# RGB_LED.net
KiCad netlist of a schematic drawn in Altium Designer
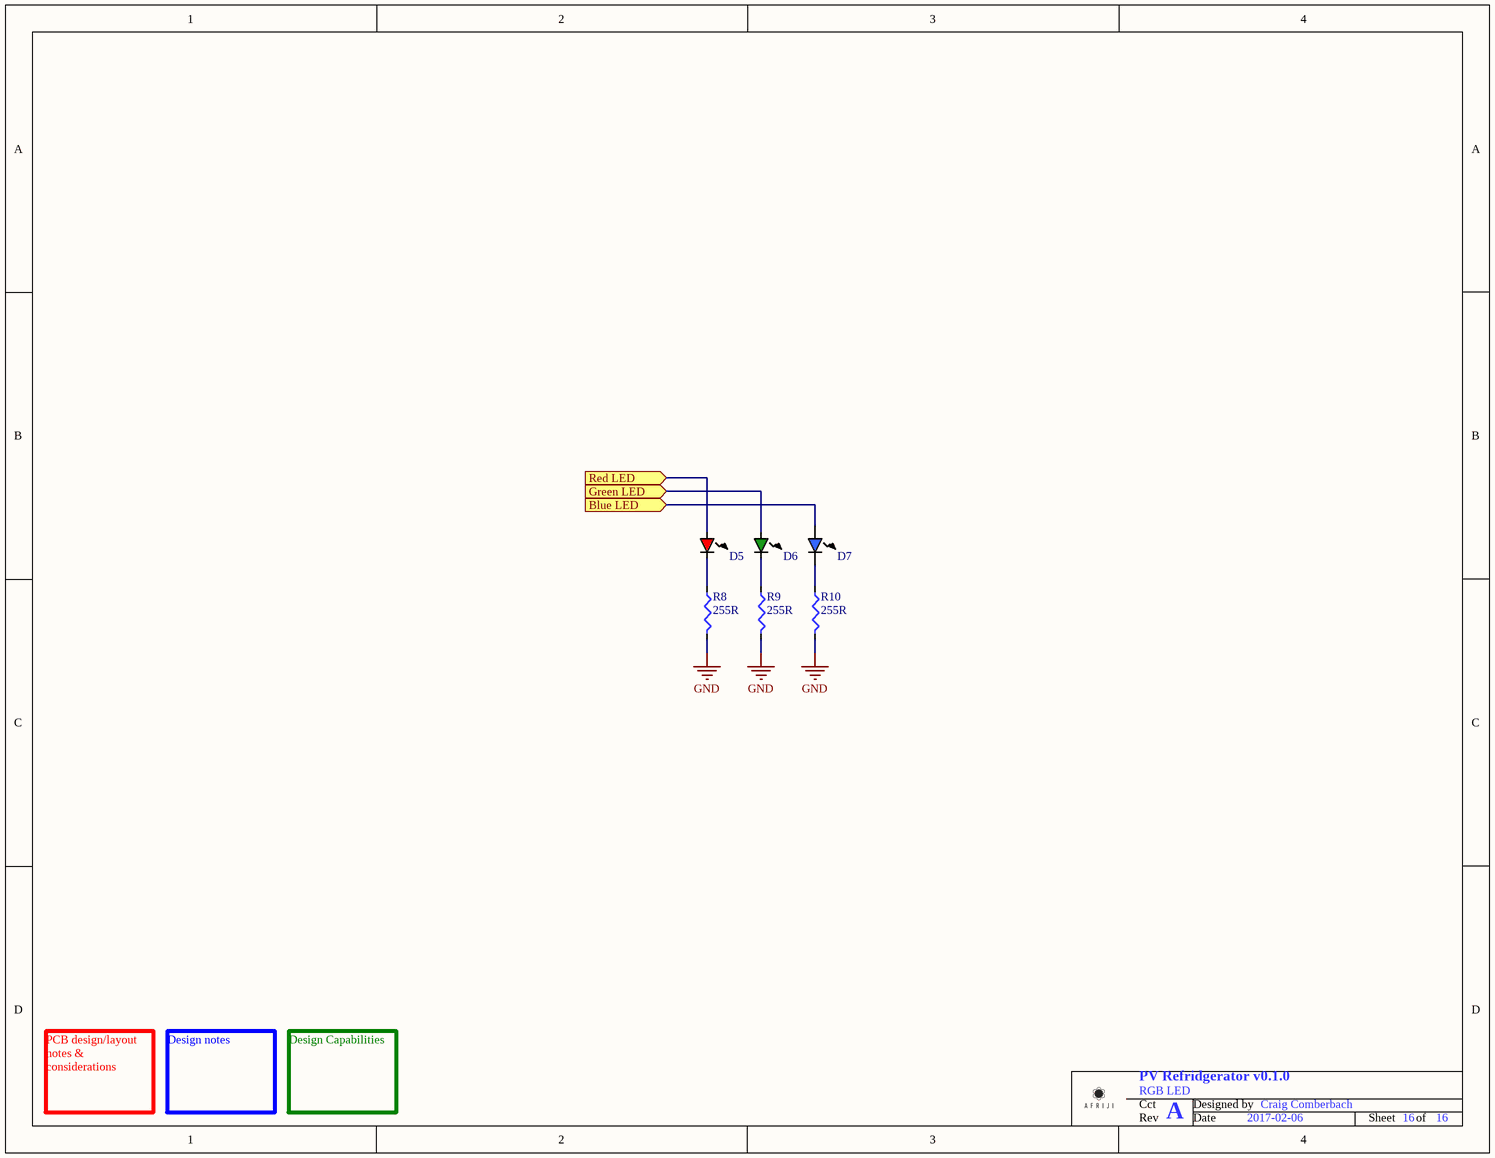
[diagram p0: RGB LED.SchDoc]

(export (version "E")
  (design (tool "Eeschema 10.0.6"))
  (components
    (comp (ref "D5")
      (value "Red LED 1206")
      (footprint "LED - 1206 Red")
      (fields
        (field (name "MANUFACTURER") "Kingbright")
        (field (name "MANUFACTURER PART NUMBER") "APT3216SRCPRV")
      )
      (libsource (lib "Personal Library") (part "Red LED 1206"))
    )
    (comp (ref "D6")
      (value "Green LED 1206")
      (footprint "LED - 1206 Green")
      (fields
        (field (name "MANUFACTURER") "Kingbright")
        (field (name "MANUFACTURER PART NUMBER") "APL3015SGC-F01")
      )
      (libsource (lib "Personal Library") (part "Green LED 1206"))
    )
    (comp (ref "D7")
      (value "Blue LED 1206")
      (footprint "LED - 1206 Blue")
      (description "Single Colour")
      (fields
        (field (name "MANUFACTURER") "Lite-On Inc")
        (field (name "MANUFACTURER PART NUMBER") "LTST-C150TBKT")
      )
      (libsource (lib "altium-import") (part "root_3_Blue LED 1206_"))
    )
    (comp (ref "R8")
      (value "255R 0805 1%")
      (footprint "R0805")
      (description "1/8W")
      (fields
        (field (name "MANUFACTURER") "Panasonic Electronic Components")
        (field (name "MANUFACTURER PART NUMBER") "ERJ-6ENF2550V")
        (field (name "RESISTANCE (OHMS)") "255R")
      )
      (libsource (lib "Personal Library") (part "255R 0805 1%"))
    )
    (comp (ref "R9")
      (value "255R 0805 1%")
      (footprint "R0805")
      (description "1/8W")
      (fields
        (field (name "MANUFACTURER") "Panasonic Electronic Components")
        (field (name "MANUFACTURER PART NUMBER") "ERJ-6ENF2550V")
        (field (name "RESISTANCE (OHMS)") "255R")
      )
      (libsource (lib "Personal Library") (part "255R 0805 1%"))
    )
    (comp (ref "R10")
      (value "255R 0805 1%")
      (footprint "R0805")
      (description "1/8W")
      (fields
        (field (name "MANUFACTURER") "Panasonic Electronic Components")
        (field (name "MANUFACTURER PART NUMBER") "ERJ-6ENF2550V")
        (field (name "RESISTANCE (OHMS)") "255R")
      )
      (libsource (lib "Personal Library") (part "255R 0805 1%"))
    )
  )
  (nets
    (net (code "1") (name "/Blue LED") (class "Default")
      (node (ref "D7") (pin "1") (pinfunction "1_1") (pintype "passive"))
    )
    (net (code "2") (name "/Green LED") (class "Default")
      (node (ref "D6") (pin "1") (pinfunction "1_1") (pintype "passive"))
    )
    (net (code "3") (name "/Red LED") (class "Default")
      (node (ref "D5") (pin "1") (pinfunction "1_1") (pintype "passive"))
    )
    (net (code "4") (name "GND") (class "Default")
      (node (ref "R10") (pin "1") (pinfunction "1_1") (pintype "passive"))
      (node (ref "R8") (pin "1") (pinfunction "1_1") (pintype "passive"))
      (node (ref "R9") (pin "1") (pinfunction "1_1") (pintype "passive"))
    )
    (net (code "5") (name "Net-(D5-Pad2)") (class "Default")
      (node (ref "D5") (pin "2") (pinfunction "2_2") (pintype "passive"))
      (node (ref "R8") (pin "2") (pinfunction "2_2") (pintype "passive"))
    )
    (net (code "6") (name "Net-(D6-Pad2)") (class "Default")
      (node (ref "D6") (pin "2") (pinfunction "2_2") (pintype "passive"))
      (node (ref "R9") (pin "2") (pinfunction "2_2") (pintype "passive"))
    )
    (net (code "7") (name "Net-(D7-Pad2)") (class "Default")
      (node (ref "D7") (pin "2") (pinfunction "2_2") (pintype "passive"))
      (node (ref "R10") (pin "2") (pinfunction "2_2") (pintype "passive"))
    )
  )
)
